# SD.net
KiCad netlist of a schematic drawn in Altium Designer
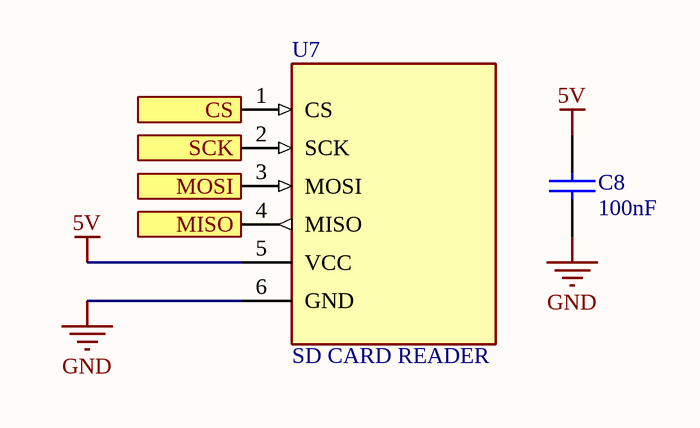
[diagram p0: SD.SchDoc]

(export (version "E")
  (design (tool "Eeschema 10.0.6"))
  (components
    (comp (ref "C8") (value "100nF") (footprint "0805") (libsource (lib "LIBPIOIX") (part "CAP")))
    (comp (ref "U7")
      (value "SD CARD READER")
      (footprint "SD CARD")
      (libsource (lib "Esquematicos") (part "SD_CARD"))
    )
  )
  (nets
    (net (code "1") (name "/CS") (class "Default")
      (node (ref "U7") (pin "1") (pinfunction "CS_1") (pintype "input"))
    )
    (net (code "2") (name "/MISO") (class "Default")
      (node (ref "U7") (pin "4") (pinfunction "MISO_4") (pintype "output"))
    )
    (net (code "3") (name "/MOSI") (class "Default")
      (node (ref "U7") (pin "3") (pinfunction "MOSI_3") (pintype "input"))
    )
    (net (code "4") (name "/SCK") (class "Default")
      (node (ref "U7") (pin "2") (pinfunction "SCK_2") (pintype "input"))
    )
    (net (code "5") (name "5V") (class "Default")
      (node (ref "C8") (pin "1") (pinfunction "1_1") (pintype "passive"))
      (node (ref "U7") (pin "5") (pinfunction "VCC_5") (pintype "power_in"))
    )
    (net (code "6") (name "GND") (class "Default")
      (node (ref "C8") (pin "2") (pinfunction "2_2") (pintype "passive"))
      (node (ref "U7") (pin "6") (pinfunction "GND_6") (pintype "power_in"))
    )
  )
)
